# receiver.net
KiCad netlist of a schematic drawn in EAGLE
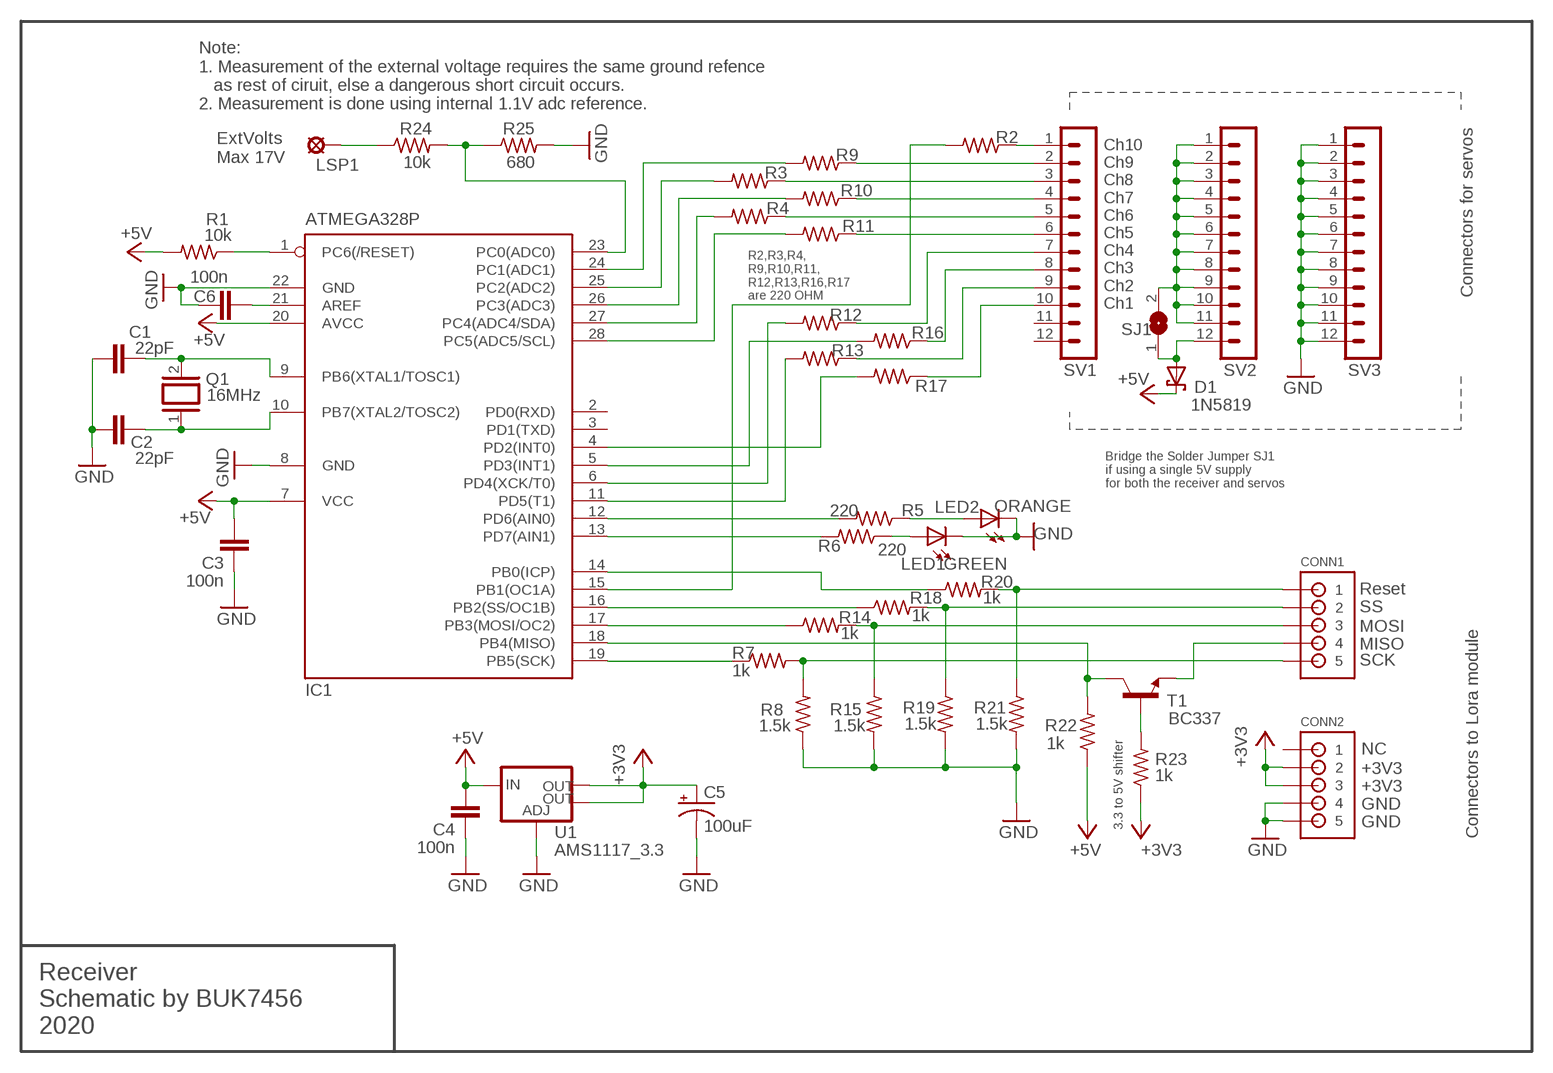
[diagram p0: schematic, sheet 1]

(export (version "E")
  (design (tool "Eeschema 10.0.6"))
  (components
    (comp (ref "C1")
      (value "22pF")
      (footprint "eagle-import:C025-025X050")
      (libsource (lib "eagle-import") (part "C-EU025-025X050"))
    )
    (comp (ref "C2")
      (value "22pF")
      (footprint "eagle-import:C025-025X050")
      (libsource (lib "eagle-import") (part "C-EU025-025X050"))
    )
    (comp (ref "C3")
      (value "100n")
      (footprint "eagle-import:C025-025X050")
      (libsource (lib "eagle-import") (part "C-EU025-025X050"))
    )
    (comp (ref "C4")
      (value "100n")
      (footprint "eagle-import:C025-025X050")
      (libsource (lib "eagle-import") (part "C-EU025-025X050"))
    )
    (comp (ref "C5")
      (value "100uF")
      (footprint "eagle-import:E2,5-6E")
      (libsource (lib "eagle-import") (part "CPOL-USE2,5-6E"))
    )
    (comp (ref "C6")
      (value "100n")
      (footprint "eagle-import:C025-025X050")
      (libsource (lib "eagle-import") (part "C-EU025-025X050"))
    )
    (comp (ref "CONN1")
      (value "JST-PH_5-PIN_HEADER")
      (footprint "eagle-import:JST_B5B-PH_HEADER")
      (libsource (lib "eagle-import") (part "JST-PH_5-PIN_HEADER"))
    )
    (comp (ref "CONN2")
      (value "JST-PH_5-PIN_HEADER")
      (footprint "eagle-import:JST_B5B-PH_HEADER")
      (libsource (lib "eagle-import") (part "JST-PH_5-PIN_HEADER"))
    )
    (comp (ref "D1")
      (value "1N5819")
      (footprint "eagle-import:DO41-7.6")
      (libsource (lib "eagle-import") (part "1N5819-T"))
    )
    (comp (ref "IC1")
      (value "ATMEGA328P")
      (footprint "eagle-import:DIL28-3")
      (libsource (lib "eagle-import") (part "MEGA8-P"))
    )
    (comp (ref "LED1")
      (value "GREEN")
      (footprint "eagle-import:LED3MM")
      (libsource (lib "eagle-import") (part "LED3MM"))
    )
    (comp (ref "LED2")
      (value "ORANGE")
      (footprint "eagle-import:LED3MM")
      (libsource (lib "eagle-import") (part "LED3MM"))
    )
    (comp (ref "LSP1")
      (value "LSP10")
      (footprint "eagle-import:LSP10")
      (libsource (lib "eagle-import") (part "LSP10"))
    )
    (comp (ref "Q1")
      (value "16MHz")
      (footprint "eagle-import:QS")
      (libsource (lib "eagle-import") (part "XTAL/S"))
    )
    (comp (ref "R1")
      (value "10k")
      (footprint "eagle-import:0204_5")
      (libsource (lib "eagle-import") (part "R-US_0204/5"))
    )
    (comp (ref "R2")
      (value "220")
      (footprint "eagle-import:0204V")
      (libsource (lib "eagle-import") (part "R-US_0204/2V"))
    )
    (comp (ref "R3")
      (value "220")
      (footprint "eagle-import:0204V")
      (libsource (lib "eagle-import") (part "R-US_0204/2V"))
    )
    (comp (ref "R4")
      (value "220")
      (footprint "eagle-import:0204V")
      (libsource (lib "eagle-import") (part "R-US_0204/2V"))
    )
    (comp (ref "R5")
      (value "220")
      (footprint "eagle-import:0204_5")
      (libsource (lib "eagle-import") (part "R-US_0204/5"))
    )
    (comp (ref "R6")
      (value "220")
      (footprint "eagle-import:0204_5")
      (libsource (lib "eagle-import") (part "R-US_0204/5"))
    )
    (comp (ref "R7")
      (value "1k")
      (footprint "eagle-import:0204_5")
      (libsource (lib "eagle-import") (part "R-US_0204/5"))
    )
    (comp (ref "R8")
      (value "1.5k")
      (footprint "eagle-import:0204V")
      (libsource (lib "eagle-import") (part "R-US_0204/2V"))
    )
    (comp (ref "R9")
      (value "220")
      (footprint "eagle-import:0204V")
      (libsource (lib "eagle-import") (part "R-US_0204/2V"))
    )
    (comp (ref "R10")
      (value "220")
      (footprint "eagle-import:0204V")
      (libsource (lib "eagle-import") (part "R-US_0204/2V"))
    )
    (comp (ref "R11")
      (value "220")
      (footprint "eagle-import:0204V")
      (libsource (lib "eagle-import") (part "R-US_0204/2V"))
    )
    (comp (ref "R12")
      (value "220")
      (footprint "eagle-import:0204V")
      (libsource (lib "eagle-import") (part "R-US_0204/2V"))
    )
    (comp (ref "R13")
      (value "220")
      (footprint "eagle-import:0204V")
      (libsource (lib "eagle-import") (part "R-US_0204/2V"))
    )
    (comp (ref "R14")
      (value "1k")
      (footprint "eagle-import:0204_5")
      (libsource (lib "eagle-import") (part "R-US_0204/5"))
    )
    (comp (ref "R15")
      (value "1.5k")
      (footprint "eagle-import:0204V")
      (libsource (lib "eagle-import") (part "R-US_0204/2V"))
    )
    (comp (ref "R16")
      (value "220")
      (footprint "eagle-import:0204V")
      (libsource (lib "eagle-import") (part "R-US_0204/2V"))
    )
    (comp (ref "R17")
      (value "220")
      (footprint "eagle-import:0204V")
      (libsource (lib "eagle-import") (part "R-US_0204/2V"))
    )
    (comp (ref "R18")
      (value "1k")
      (footprint "eagle-import:0204_5")
      (libsource (lib "eagle-import") (part "R-US_0204/5"))
    )
    (comp (ref "R19")
      (value "1.5k")
      (footprint "eagle-import:0204V")
      (libsource (lib "eagle-import") (part "R-US_0204/2V"))
    )
    (comp (ref "R20")
      (value "1k")
      (footprint "eagle-import:0204_5")
      (libsource (lib "eagle-import") (part "R-US_0204/5"))
    )
    (comp (ref "R21")
      (value "1.5k")
      (footprint "eagle-import:0204V")
      (libsource (lib "eagle-import") (part "R-US_0204/2V"))
    )
    (comp (ref "R22")
      (value "1k")
      (footprint "eagle-import:0204_7")
      (libsource (lib "eagle-import") (part "R-US_0204/7"))
    )
    (comp (ref "R23")
      (value "1k")
      (footprint "eagle-import:0204_5")
      (libsource (lib "eagle-import") (part "R-US_0204/5"))
    )
    (comp (ref "R24")
      (value "10k")
      (footprint "eagle-import:0204_5")
      (libsource (lib "eagle-import") (part "R-US_0204/5"))
    )
    (comp (ref "R25")
      (value "680")
      (footprint "eagle-import:0204_5")
      (libsource (lib "eagle-import") (part "R-US_0204/5"))
    )
    (comp (ref "SJ1") (value "SJ") (footprint "eagle-import:SJ") (libsource (lib "eagle-import") (part "SJ")))
    (comp (ref "SV1")
      (value "MA12-1")
      (footprint "eagle-import:MA12-1")
      (libsource (lib "eagle-import") (part "MA12-1"))
    )
    (comp (ref "SV2")
      (value "MA12-1")
      (footprint "eagle-import:MA12-1")
      (libsource (lib "eagle-import") (part "MA12-1"))
    )
    (comp (ref "SV3")
      (value "MA12-1")
      (footprint "eagle-import:MA12-1")
      (libsource (lib "eagle-import") (part "MA12-1"))
    )
    (comp (ref "T1")
      (value "BC337")
      (footprint "eagle-import:TO92")
      (libsource (lib "eagle-import") (part "BC337"))
    )
    (comp (ref "U1")
      (value "AMS1117_3.3")
      (footprint "eagle-import:SOT223")
      (libsource (lib "eagle-import") (part "V_REG_LM1117SOT223"))
    )
  )
  (nets
    (net (code "1") (name "+3V3") (class "Default")
      (node (ref "C5") (pin "+") (pinfunction "+_+") (pintype "passive"))
      (node (ref "CONN2") (pin "P2") (pinfunction "2_P2") (pintype "bidirectional"))
      (node (ref "CONN2") (pin "P3") (pinfunction "3_P3") (pintype "bidirectional"))
      (node (ref "R23") (pin "1") (pinfunction "1_1") (pintype "passive"))
      (node (ref "U1") (pin "2") (pinfunction "OUT_2") (pintype "output"))
      (node (ref "U1") (pin "4") (pinfunction "OUT_4") (pintype "output"))
    )
    (net (code "2") (name "+5V") (class "Default")
      (node (ref "C3") (pin "2") (pinfunction "2_2") (pintype "passive"))
      (node (ref "C4") (pin "2") (pinfunction "2_2") (pintype "passive"))
      (node (ref "D1") (pin "C") (pinfunction "C_C") (pintype "passive"))
      (node (ref "IC1") (pin "20") (pinfunction "AVCC_20") (pintype "power_in"))
      (node (ref "IC1") (pin "7") (pinfunction "VCC_7") (pintype "power_in"))
      (node (ref "R1") (pin "2") (pinfunction "2_2") (pintype "passive"))
      (node (ref "R22") (pin "1") (pinfunction "1_1") (pintype "passive"))
      (node (ref "U1") (pin "3") (pinfunction "IN_3") (pintype "input"))
    )
    (net (code "3") (name "GND") (class "Default")
      (node (ref "C1") (pin "1") (pinfunction "1_1") (pintype "passive"))
      (node (ref "C2") (pin "1") (pinfunction "1_1") (pintype "passive"))
      (node (ref "C3") (pin "1") (pinfunction "1_1") (pintype "passive"))
      (node (ref "C4") (pin "1") (pinfunction "1_1") (pintype "passive"))
      (node (ref "C5") (pin "-") (pinfunction "-_-") (pintype "passive"))
      (node (ref "C6") (pin "2") (pinfunction "2_2") (pintype "passive"))
      (node (ref "CONN2") (pin "P4") (pinfunction "4_P4") (pintype "bidirectional"))
      (node (ref "CONN2") (pin "P5") (pinfunction "5_P5") (pintype "bidirectional"))
      (node (ref "IC1") (pin "22") (pinfunction "GND_22") (pintype "power_in"))
      (node (ref "IC1") (pin "8") (pinfunction "GND_8") (pintype "power_in"))
      (node (ref "LED1") (pin "K") (pinfunction "C_K") (pintype "passive"))
      (node (ref "LED2") (pin "K") (pinfunction "C_K") (pintype "passive"))
      (node (ref "R15") (pin "2") (pinfunction "2_2") (pintype "passive"))
      (node (ref "R19") (pin "2") (pinfunction "2_2") (pintype "passive"))
      (node (ref "R21") (pin "2") (pinfunction "2_2") (pintype "passive"))
      (node (ref "R25") (pin "2") (pinfunction "2_2") (pintype "passive"))
      (node (ref "R8") (pin "1") (pinfunction "1_1") (pintype "passive"))
      (node (ref "SV3") (pin "1") (pinfunction "1_1") (pintype "passive"))
      (node (ref "SV3") (pin "10") (pinfunction "10_10") (pintype "passive"))
      (node (ref "SV3") (pin "11") (pinfunction "11_11") (pintype "passive"))
      (node (ref "SV3") (pin "12") (pinfunction "12_12") (pintype "passive"))
      (node (ref "SV3") (pin "2") (pinfunction "2_2") (pintype "passive"))
      (node (ref "SV3") (pin "3") (pinfunction "3_3") (pintype "passive"))
      (node (ref "SV3") (pin "4") (pinfunction "4_4") (pintype "passive"))
      (node (ref "SV3") (pin "5") (pinfunction "5_5") (pintype "passive"))
      (node (ref "SV3") (pin "6") (pinfunction "6_6") (pintype "passive"))
      (node (ref "SV3") (pin "7") (pinfunction "7_7") (pintype "passive"))
      (node (ref "SV3") (pin "8") (pinfunction "8_8") (pintype "passive"))
      (node (ref "SV3") (pin "9") (pinfunction "9_9") (pintype "passive"))
      (node (ref "U1") (pin "1") (pinfunction "ADJ_1") (pintype "input"))
    )
    (net (code "4") (name "Net-(CONN1-1)") (class "Default")
      (node (ref "CONN1") (pin "P1") (pinfunction "1_P1") (pintype "bidirectional"))
      (node (ref "R20") (pin "2") (pinfunction "2_2") (pintype "passive"))
      (node (ref "R21") (pin "1") (pinfunction "1_1") (pintype "passive"))
    )
    (net (code "5") (name "Net-(CONN1-2)") (class "Default")
      (node (ref "CONN1") (pin "P2") (pinfunction "2_P2") (pintype "bidirectional"))
      (node (ref "R18") (pin "2") (pinfunction "2_2") (pintype "passive"))
      (node (ref "R19") (pin "1") (pinfunction "1_1") (pintype "passive"))
    )
    (net (code "6") (name "Net-(CONN1-3)") (class "Default")
      (node (ref "CONN1") (pin "P3") (pinfunction "3_P3") (pintype "bidirectional"))
      (node (ref "R14") (pin "2") (pinfunction "2_2") (pintype "passive"))
      (node (ref "R15") (pin "1") (pinfunction "1_1") (pintype "passive"))
    )
    (net (code "7") (name "Net-(CONN1-4)") (class "Default")
      (node (ref "CONN1") (pin "P4") (pinfunction "4_P4") (pintype "bidirectional"))
      (node (ref "T1") (pin "1") (pinfunction "E_1") (pintype "passive"))
    )
    (net (code "8") (name "Net-(CONN1-5)") (class "Default")
      (node (ref "CONN1") (pin "P5") (pinfunction "5_P5") (pintype "bidirectional"))
      (node (ref "R7") (pin "2") (pinfunction "2_2") (pintype "passive"))
      (node (ref "R8") (pin "2") (pinfunction "2_2") (pintype "passive"))
    )
    (net (code "9") (name "Net-(D1-PadA)") (class "Default")
      (node (ref "D1") (pin "A") (pinfunction "A_A") (pintype "passive"))
      (node (ref "SJ1") (pin "1") (pinfunction "1_1") (pintype "passive"))
      (node (ref "SV2") (pin "12") (pinfunction "12_12") (pintype "passive"))
    )
    (net (code "10") (name "Net-(IC1-AREF)") (class "Default")
      (node (ref "C6") (pin "1") (pinfunction "1_1") (pintype "passive"))
      (node (ref "IC1") (pin "21") (pinfunction "AREF_21") (pintype "passive"))
    )
    (net (code "11") (name "Net-(IC1-PB0(ICP))") (class "Default")
      (node (ref "IC1") (pin "14") (pinfunction "PB0(ICP)_14") (pintype "bidirectional"))
      (node (ref "R20") (pin "1") (pinfunction "1_1") (pintype "passive"))
    )
    (net (code "12") (name "Net-(IC1-PB1(OC1A))") (class "Default")
      (node (ref "IC1") (pin "15") (pinfunction "PB1(OC1A)_15") (pintype "bidirectional"))
      (node (ref "R2") (pin "2") (pinfunction "2_2") (pintype "passive"))
    )
    (net (code "13") (name "Net-(IC1-PB2(SS{slash}OC1B))") (class "Default")
      (node (ref "IC1") (pin "16") (pinfunction "PB2(SS/OC1B)_16") (pintype "bidirectional"))
      (node (ref "R18") (pin "1") (pinfunction "1_1") (pintype "passive"))
    )
    (net (code "14") (name "Net-(IC1-PB3(MOSI{slash}OC2))") (class "Default")
      (node (ref "IC1") (pin "17") (pinfunction "PB3(MOSI/OC2)_17") (pintype "bidirectional"))
      (node (ref "R14") (pin "1") (pinfunction "1_1") (pintype "passive"))
    )
    (net (code "15") (name "Net-(IC1-PB4(MISO))") (class "Default")
      (node (ref "IC1") (pin "18") (pinfunction "PB4(MISO)_18") (pintype "bidirectional"))
      (node (ref "R22") (pin "2") (pinfunction "2_2") (pintype "passive"))
      (node (ref "T1") (pin "3") (pinfunction "C_3") (pintype "passive"))
    )
    (net (code "16") (name "Net-(IC1-PB5(SCK))") (class "Default")
      (node (ref "IC1") (pin "19") (pinfunction "PB5(SCK)_19") (pintype "bidirectional"))
      (node (ref "R7") (pin "1") (pinfunction "1_1") (pintype "passive"))
    )
    (net (code "17") (name "Net-(IC1-PB6(XTAL1{slash}TOSC1))") (class "Default")
      (node (ref "C1") (pin "2") (pinfunction "2_2") (pintype "passive"))
      (node (ref "IC1") (pin "9") (pinfunction "PB6(XTAL1/TOSC1)_9") (pintype "bidirectional"))
      (node (ref "Q1") (pin "2") (pinfunction "2_2") (pintype "passive"))
    )
    (net (code "18") (name "Net-(IC1-PB7(XTAL2{slash}TOSC2))") (class "Default")
      (node (ref "C2") (pin "2") (pinfunction "2_2") (pintype "passive"))
      (node (ref "IC1") (pin "10") (pinfunction "PB7(XTAL2/TOSC2)_10") (pintype "bidirectional"))
      (node (ref "Q1") (pin "1") (pinfunction "1_1") (pintype "passive"))
    )
    (net (code "19") (name "Net-(IC1-PC0(ADC0))") (class "Default")
      (node (ref "IC1") (pin "23") (pinfunction "PC0(ADC0)_23") (pintype "bidirectional"))
      (node (ref "R24") (pin "2") (pinfunction "2_2") (pintype "passive"))
      (node (ref "R25") (pin "1") (pinfunction "1_1") (pintype "passive"))
    )
    (net (code "20") (name "Net-(IC1-PC1(ADC1))") (class "Default")
      (node (ref "IC1") (pin "24") (pinfunction "PC1(ADC1)_24") (pintype "bidirectional"))
      (node (ref "R9") (pin "2") (pinfunction "2_2") (pintype "passive"))
    )
    (net (code "21") (name "Net-(IC1-PC2(ADC2))") (class "Default")
      (node (ref "IC1") (pin "25") (pinfunction "PC2(ADC2)_25") (pintype "bidirectional"))
      (node (ref "R3") (pin "2") (pinfunction "2_2") (pintype "passive"))
    )
    (net (code "22") (name "Net-(IC1-PC3(ADC3))") (class "Default")
      (node (ref "IC1") (pin "26") (pinfunction "PC3(ADC3)_26") (pintype "bidirectional"))
      (node (ref "R10") (pin "2") (pinfunction "2_2") (pintype "passive"))
    )
    (net (code "23") (name "Net-(IC1-PC4(ADC4{slash}SDA))") (class "Default")
      (node (ref "IC1") (pin "27") (pinfunction "PC4(ADC4/SDA)_27") (pintype "bidirectional"))
      (node (ref "R4") (pin "2") (pinfunction "2_2") (pintype "passive"))
    )
    (net (code "24") (name "Net-(IC1-PC5(ADC5{slash}SCL))") (class "Default")
      (node (ref "IC1") (pin "28") (pinfunction "PC5(ADC5/SCL)_28") (pintype "bidirectional"))
      (node (ref "R11") (pin "2") (pinfunction "2_2") (pintype "passive"))
    )
    (net (code "25") (name "Net-(IC1-PC6({slash}RESET))") (class "Default")
      (node (ref "IC1") (pin "1") (pinfunction "PC6(/RESET)_1") (pintype "bidirectional"))
      (node (ref "R1") (pin "1") (pinfunction "1_1") (pintype "passive"))
    )
    (net (code "26") (name "Net-(IC1-PD2(INT0))") (class "Default")
      (node (ref "IC1") (pin "4") (pinfunction "PD2(INT0)_4") (pintype "bidirectional"))
      (node (ref "R17") (pin "2") (pinfunction "2_2") (pintype "passive"))
    )
    (net (code "27") (name "Net-(IC1-PD3(INT1))") (class "Default")
      (node (ref "IC1") (pin "5") (pinfunction "PD3(INT1)_5") (pintype "bidirectional"))
      (node (ref "R16") (pin "2") (pinfunction "2_2") (pintype "passive"))
    )
    (net (code "28") (name "Net-(IC1-PD4(XCK{slash}T0))") (class "Default")
      (node (ref "IC1") (pin "6") (pinfunction "PD4(XCK/T0)_6") (pintype "bidirectional"))
      (node (ref "R12") (pin "2") (pinfunction "2_2") (pintype "passive"))
    )
    (net (code "29") (name "Net-(IC1-PD5(T1))") (class "Default")
      (node (ref "IC1") (pin "11") (pinfunction "PD5(T1)_11") (pintype "bidirectional"))
      (node (ref "R13") (pin "2") (pinfunction "2_2") (pintype "passive"))
    )
    (net (code "30") (name "Net-(IC1-PD6(AIN0))") (class "Default")
      (node (ref "IC1") (pin "12") (pinfunction "PD6(AIN0)_12") (pintype "bidirectional"))
      (node (ref "R5") (pin "2") (pinfunction "2_2") (pintype "passive"))
    )
    (net (code "31") (name "Net-(IC1-PD7(AIN1))") (class "Default")
      (node (ref "IC1") (pin "13") (pinfunction "PD7(AIN1)_13") (pintype "bidirectional"))
      (node (ref "R6") (pin "2") (pinfunction "2_2") (pintype "passive"))
    )
    (net (code "32") (name "Net-(LED1-PadA)") (class "Default")
      (node (ref "LED1") (pin "A") (pinfunction "A_A") (pintype "passive"))
      (node (ref "R6") (pin "1") (pinfunction "1_1") (pintype "passive"))
    )
    (net (code "33") (name "Net-(LED2-PadA)") (class "Default")
      (node (ref "LED2") (pin "A") (pinfunction "A_A") (pintype "passive"))
      (node (ref "R5") (pin "1") (pinfunction "1_1") (pintype "passive"))
    )
    (net (code "34") (name "Net-(LSP1-PadMP)") (class "Default")
      (node (ref "LSP1") (pin "MP") (pinfunction "MP_MP") (pintype "passive"))
      (node (ref "R24") (pin "1") (pinfunction "1_1") (pintype "passive"))
    )
    (net (code "35") (name "Net-(R2-Pad1)") (class "Default")
      (node (ref "R2") (pin "1") (pinfunction "1_1") (pintype "passive"))
      (node (ref "SV1") (pin "1") (pinfunction "1_1") (pintype "passive"))
    )
    (net (code "36") (name "Net-(R3-Pad1)") (class "Default")
      (node (ref "R3") (pin "1") (pinfunction "1_1") (pintype "passive"))
      (node (ref "SV1") (pin "3") (pinfunction "3_3") (pintype "passive"))
    )
    (net (code "37") (name "Net-(R4-Pad1)") (class "Default")
      (node (ref "R4") (pin "1") (pinfunction "1_1") (pintype "passive"))
      (node (ref "SV1") (pin "5") (pinfunction "5_5") (pintype "passive"))
    )
    (net (code "38") (name "Net-(R9-Pad1)") (class "Default")
      (node (ref "R9") (pin "1") (pinfunction "1_1") (pintype "passive"))
      (node (ref "SV1") (pin "2") (pinfunction "2_2") (pintype "passive"))
    )
    (net (code "39") (name "Net-(R10-Pad1)") (class "Default")
      (node (ref "R10") (pin "1") (pinfunction "1_1") (pintype "passive"))
      (node (ref "SV1") (pin "4") (pinfunction "4_4") (pintype "passive"))
    )
    (net (code "40") (name "Net-(R11-Pad1)") (class "Default")
      (node (ref "R11") (pin "1") (pinfunction "1_1") (pintype "passive"))
      (node (ref "SV1") (pin "6") (pinfunction "6_6") (pintype "passive"))
    )
    (net (code "41") (name "Net-(R12-Pad1)") (class "Default")
      (node (ref "R12") (pin "1") (pinfunction "1_1") (pintype "passive"))
      (node (ref "SV1") (pin "7") (pinfunction "7_7") (pintype "passive"))
    )
    (net (code "42") (name "Net-(R13-Pad1)") (class "Default")
      (node (ref "R13") (pin "1") (pinfunction "1_1") (pintype "passive"))
      (node (ref "SV1") (pin "9") (pinfunction "9_9") (pintype "passive"))
    )
    (net (code "43") (name "Net-(R16-Pad1)") (class "Default")
      (node (ref "R16") (pin "1") (pinfunction "1_1") (pintype "passive"))
      (node (ref "SV1") (pin "8") (pinfunction "8_8") (pintype "passive"))
    )
    (net (code "44") (name "Net-(R17-Pad1)") (class "Default")
      (node (ref "R17") (pin "1") (pinfunction "1_1") (pintype "passive"))
      (node (ref "SV1") (pin "10") (pinfunction "10_10") (pintype "passive"))
    )
    (net (code "45") (name "Net-(SJ1-Pad2)") (class "Default")
      (node (ref "SJ1") (pin "2") (pinfunction "2_2") (pintype "passive"))
      (node (ref "SV2") (pin "1") (pinfunction "1_1") (pintype "passive"))
      (node (ref "SV2") (pin "10") (pinfunction "10_10") (pintype "passive"))
      (node (ref "SV2") (pin "11") (pinfunction "11_11") (pintype "passive"))
      (node (ref "SV2") (pin "2") (pinfunction "2_2") (pintype "passive"))
      (node (ref "SV2") (pin "3") (pinfunction "3_3") (pintype "passive"))
      (node (ref "SV2") (pin "4") (pinfunction "4_4") (pintype "passive"))
      (node (ref "SV2") (pin "5") (pinfunction "5_5") (pintype "passive"))
      (node (ref "SV2") (pin "6") (pinfunction "6_6") (pintype "passive"))
      (node (ref "SV2") (pin "7") (pinfunction "7_7") (pintype "passive"))
      (node (ref "SV2") (pin "8") (pinfunction "8_8") (pintype "passive"))
      (node (ref "SV2") (pin "9") (pinfunction "9_9") (pintype "passive"))
    )
    (net (code "46") (name "Net-(T1-B)") (class "Default")
      (node (ref "R23") (pin "2") (pinfunction "2_2") (pintype "passive"))
      (node (ref "T1") (pin "2") (pinfunction "B_2") (pintype "passive"))
    )
    (net (code "47") (name "unconnected-(CONN2-1-PadP1)") (class "Default")
      (node (ref "CONN2") (pin "P1") (pinfunction "1_P1") (pintype "bidirectional"))
    )
    (net (code "48") (name "unconnected-(IC1-PD0(RXD)-Pad2)") (class "Default")
      (node (ref "IC1") (pin "2") (pinfunction "PD0(RXD)_2") (pintype "bidirectional"))
    )
    (net (code "49") (name "unconnected-(IC1-PD1(TXD)-Pad3)") (class "Default")
      (node (ref "IC1") (pin "3") (pinfunction "PD1(TXD)_3") (pintype "bidirectional"))
    )
    (net (code "50") (name "unconnected-(SV1-Pad11)") (class "Default")
      (node (ref "SV1") (pin "11") (pinfunction "11_11") (pintype "passive"))
    )
    (net (code "51") (name "unconnected-(SV1-Pad12)") (class "Default")
      (node (ref "SV1") (pin "12") (pinfunction "12_12") (pintype "passive"))
    )
  )
)
